# USB_to_Serial.net
KiCad netlist of a schematic drawn in EAGLE
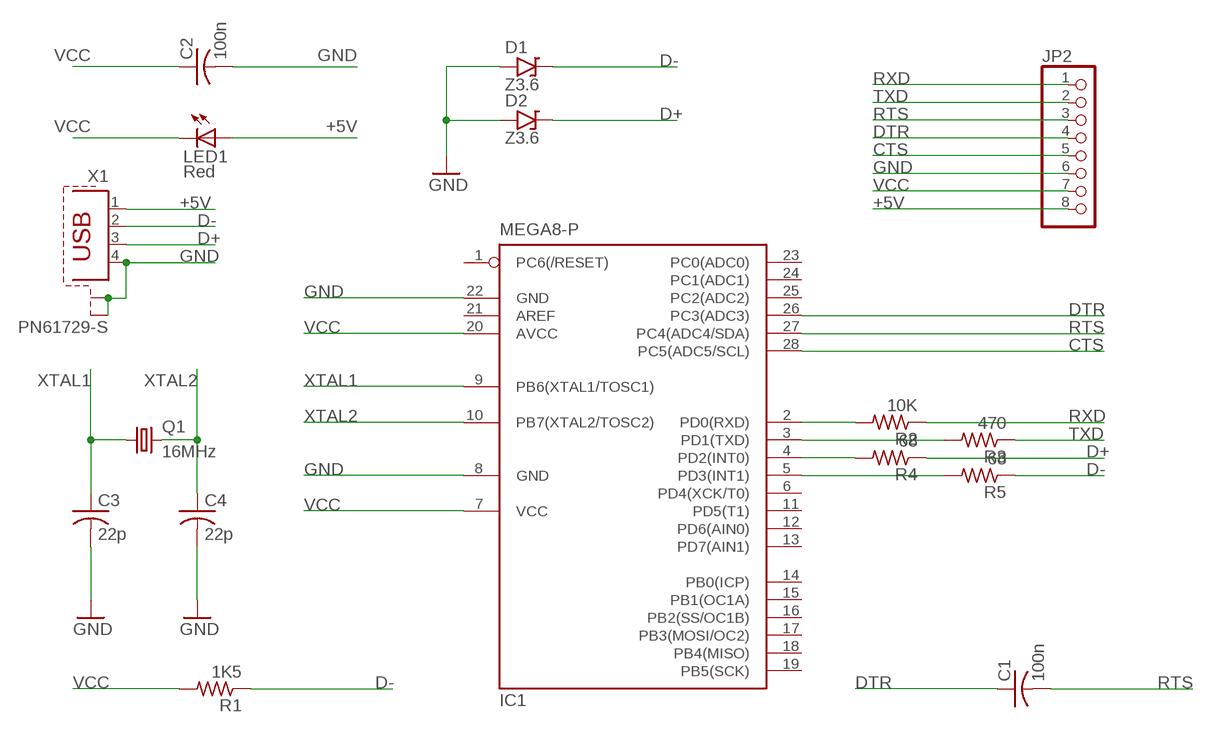
[diagram p0: schematic, sheet 1]

(export (version "E")
  (design (tool "Eeschema 10.0.6"))
  (components
    (comp (ref "C1")
      (value "100n")
      (footprint "eagle-import:C050-024X044")
      (libsource (lib "eagle-import") (part "C-US050-024X044"))
    )
    (comp (ref "C2")
      (value "100n")
      (footprint "eagle-import:C050-024X044")
      (libsource (lib "eagle-import") (part "C-US050-024X044"))
    )
    (comp (ref "C3")
      (value "22p")
      (footprint "eagle-import:C050-024X044")
      (libsource (lib "eagle-import") (part "C-US050-024X044"))
    )
    (comp (ref "C4")
      (value "22p")
      (footprint "eagle-import:C050-024X044")
      (libsource (lib "eagle-import") (part "C-US050-024X044"))
    )
    (comp (ref "D1")
      (value "Z3.6")
      (footprint "eagle-import:DO35-3")
      (libsource (lib "eagle-import") (part "1N9ZENER"))
    )
    (comp (ref "D2")
      (value "Z3.6")
      (footprint "eagle-import:DO35-3")
      (libsource (lib "eagle-import") (part "1N9ZENER"))
    )
    (comp (ref "IC1")
      (value "MEGA8-P")
      (footprint "eagle-import:DIL28-3")
      (libsource (lib "eagle-import") (part "MEGA8-P"))
    )
    (comp (ref "JP2")
      (value "PINHD-1X8/90")
      (footprint "eagle-import:1X08_90")
      (libsource (lib "eagle-import") (part "PINHD-1X8/90"))
    )
    (comp (ref "LED1")
      (value "Red")
      (footprint "eagle-import:LED3MM")
      (libsource (lib "eagle-import") (part "LED3MM"))
    )
    (comp (ref "Q1")
      (value "16MHz")
      (footprint "eagle-import:HC49_S")
      (libsource (lib "eagle-import") (part "CRYSTALHC49S"))
    )
    (comp (ref "R1")
      (value "1K5")
      (footprint "eagle-import:0207_7")
      (libsource (lib "eagle-import") (part "R-US_0207/7"))
    )
    (comp (ref "R2")
      (value "10K")
      (footprint "eagle-import:0207_7")
      (libsource (lib "eagle-import") (part "R-US_0207/7"))
    )
    (comp (ref "R3")
      (value "470")
      (footprint "eagle-import:0207_7")
      (libsource (lib "eagle-import") (part "R-US_0207/7"))
    )
    (comp (ref "R4")
      (value "68")
      (footprint "eagle-import:0207_7")
      (libsource (lib "eagle-import") (part "R-US_0207/7"))
    )
    (comp (ref "R5")
      (value "68")
      (footprint "eagle-import:0207_7")
      (libsource (lib "eagle-import") (part "R-US_0207/7"))
    )
    (comp (ref "X1")
      (value "PN61729-S")
      (footprint "eagle-import:PN61729-S")
      (libsource (lib "eagle-import") (part "PN61729-S"))
    )
  )
  (nets
    (net (code "1") (name "/+5V") (class "Default")
      (node (ref "JP2") (pin "8") (pinfunction "8_8") (pintype "passive"))
      (node (ref "LED1") (pin "A") (pinfunction "A_A") (pintype "passive"))
      (node (ref "X1") (pin "1") (pinfunction "1_1") (pintype "passive"))
    )
    (net (code "2") (name "/CTS") (class "Default")
      (node (ref "IC1") (pin "28") (pinfunction "PC5(ADC5/SCL)_28") (pintype "bidirectional"))
      (node (ref "JP2") (pin "5") (pinfunction "5_5") (pintype "passive"))
    )
    (net (code "3") (name "/D+") (class "Default")
      (node (ref "D2") (pin "C") (pinfunction "C_C") (pintype "passive"))
      (node (ref "R4") (pin "1") (pinfunction "1_1") (pintype "passive"))
      (node (ref "X1") (pin "3") (pinfunction "3_3") (pintype "passive"))
    )
    (net (code "4") (name "/D-") (class "Default")
      (node (ref "D1") (pin "C") (pinfunction "C_C") (pintype "passive"))
      (node (ref "R1") (pin "1") (pinfunction "1_1") (pintype "passive"))
      (node (ref "R5") (pin "1") (pinfunction "1_1") (pintype "passive"))
      (node (ref "X1") (pin "2") (pinfunction "2_2") (pintype "passive"))
    )
    (net (code "5") (name "/DTR") (class "Default")
      (node (ref "C1") (pin "1") (pinfunction "1_1") (pintype "passive"))
      (node (ref "IC1") (pin "26") (pinfunction "PC3(ADC3)_26") (pintype "bidirectional"))
      (node (ref "JP2") (pin "4") (pinfunction "4_4") (pintype "passive"))
    )
    (net (code "6") (name "/RTS") (class "Default")
      (node (ref "C1") (pin "2") (pinfunction "2_2") (pintype "passive"))
      (node (ref "IC1") (pin "27") (pinfunction "PC4(ADC4/SDA)_27") (pintype "bidirectional"))
      (node (ref "JP2") (pin "3") (pinfunction "3_3") (pintype "passive"))
    )
    (net (code "7") (name "/RXD") (class "Default")
      (node (ref "JP2") (pin "1") (pinfunction "1_1") (pintype "passive"))
      (node (ref "R2") (pin "1") (pinfunction "1_1") (pintype "passive"))
    )
    (net (code "8") (name "/TXD") (class "Default")
      (node (ref "JP2") (pin "2") (pinfunction "2_2") (pintype "passive"))
      (node (ref "R3") (pin "1") (pinfunction "1_1") (pintype "passive"))
    )
    (net (code "9") (name "/VCC") (class "Default")
      (node (ref "C2") (pin "1") (pinfunction "1_1") (pintype "passive"))
      (node (ref "IC1") (pin "20") (pinfunction "AVCC_20") (pintype "power_in"))
      (node (ref "IC1") (pin "7") (pinfunction "VCC_7") (pintype "power_in"))
      (node (ref "JP2") (pin "7") (pinfunction "7_7") (pintype "passive"))
      (node (ref "LED1") (pin "K") (pinfunction "C_K") (pintype "passive"))
      (node (ref "R1") (pin "2") (pinfunction "2_2") (pintype "passive"))
    )
    (net (code "10") (name "/XTAL1") (class "Default")
      (node (ref "C3") (pin "1") (pinfunction "1_1") (pintype "passive"))
      (node (ref "IC1") (pin "9") (pinfunction "PB6(XTAL1/TOSC1)_9") (pintype "bidirectional"))
      (node (ref "Q1") (pin "1") (pinfunction "1_1") (pintype "passive"))
    )
    (net (code "11") (name "/XTAL2") (class "Default")
      (node (ref "C4") (pin "1") (pinfunction "1_1") (pintype "passive"))
      (node (ref "IC1") (pin "10") (pinfunction "PB7(XTAL2/TOSC2)_10") (pintype "bidirectional"))
      (node (ref "Q1") (pin "2") (pinfunction "2_2") (pintype "passive"))
    )
    (net (code "12") (name "GND") (class "Default")
      (node (ref "C2") (pin "2") (pinfunction "2_2") (pintype "passive"))
      (node (ref "C3") (pin "2") (pinfunction "2_2") (pintype "passive"))
      (node (ref "C4") (pin "2") (pinfunction "2_2") (pintype "passive"))
      (node (ref "D1") (pin "A") (pinfunction "A_A") (pintype "passive"))
      (node (ref "D2") (pin "A") (pinfunction "A_A") (pintype "passive"))
      (node (ref "IC1") (pin "22") (pinfunction "GND_22") (pintype "power_in"))
      (node (ref "IC1") (pin "8") (pinfunction "GND_8") (pintype "power_in"))
      (node (ref "JP2") (pin "6") (pinfunction "6_6") (pintype "passive"))
      (node (ref "X1") (pin "4") (pinfunction "4_4") (pintype "passive"))
      (node (ref "X1") (pin "S1") (pinfunction "S1_S1") (pintype "passive"))
      (node (ref "X1") (pin "S2") (pinfunction "S2_S2") (pintype "passive"))
    )
    (net (code "13") (name "Net-(IC1-PD0(RXD))") (class "Default")
      (node (ref "IC1") (pin "2") (pinfunction "PD0(RXD)_2") (pintype "bidirectional"))
      (node (ref "R2") (pin "2") (pinfunction "2_2") (pintype "passive"))
    )
    (net (code "14") (name "Net-(IC1-PD1(TXD))") (class "Default")
      (node (ref "IC1") (pin "3") (pinfunction "PD1(TXD)_3") (pintype "bidirectional"))
      (node (ref "R3") (pin "2") (pinfunction "2_2") (pintype "passive"))
    )
    (net (code "15") (name "Net-(IC1-PD2(INT0))") (class "Default")
      (node (ref "IC1") (pin "4") (pinfunction "PD2(INT0)_4") (pintype "bidirectional"))
      (node (ref "R4") (pin "2") (pinfunction "2_2") (pintype "passive"))
    )
    (net (code "16") (name "Net-(IC1-PD3(INT1))") (class "Default")
      (node (ref "IC1") (pin "5") (pinfunction "PD3(INT1)_5") (pintype "bidirectional"))
      (node (ref "R5") (pin "2") (pinfunction "2_2") (pintype "passive"))
    )
    (net (code "17") (name "unconnected-(IC1-AREF-Pad21)") (class "Default")
      (node (ref "IC1") (pin "21") (pinfunction "AREF_21") (pintype "passive"))
    )
    (net (code "18") (name "unconnected-(IC1-PB0(ICP)-Pad14)") (class "Default")
      (node (ref "IC1") (pin "14") (pinfunction "PB0(ICP)_14") (pintype "bidirectional"))
    )
    (net (code "19") (name "unconnected-(IC1-PB1(OC1A)-Pad15)") (class "Default")
      (node (ref "IC1") (pin "15") (pinfunction "PB1(OC1A)_15") (pintype "bidirectional"))
    )
    (net (code "20") (name "unconnected-(IC1-PB2(SS{slash}OC1B)-Pad16)") (class "Default")
      (node (ref "IC1") (pin "16") (pinfunction "PB2(SS/OC1B)_16") (pintype "bidirectional"))
    )
    (net (code "21") (name "unconnected-(IC1-PB3(MOSI{slash}OC2)-Pad17)") (class "Default")
      (node (ref "IC1") (pin "17") (pinfunction "PB3(MOSI/OC2)_17") (pintype "bidirectional"))
    )
    (net (code "22") (name "unconnected-(IC1-PB4(MISO)-Pad18)") (class "Default")
      (node (ref "IC1") (pin "18") (pinfunction "PB4(MISO)_18") (pintype "bidirectional"))
    )
    (net (code "23") (name "unconnected-(IC1-PB5(SCK)-Pad19)") (class "Default")
      (node (ref "IC1") (pin "19") (pinfunction "PB5(SCK)_19") (pintype "bidirectional"))
    )
    (net (code "24") (name "unconnected-(IC1-PC0(ADC0)-Pad23)") (class "Default")
      (node (ref "IC1") (pin "23") (pinfunction "PC0(ADC0)_23") (pintype "bidirectional"))
    )
    (net (code "25") (name "unconnected-(IC1-PC1(ADC1)-Pad24)") (class "Default")
      (node (ref "IC1") (pin "24") (pinfunction "PC1(ADC1)_24") (pintype "bidirectional"))
    )
    (net (code "26") (name "unconnected-(IC1-PC2(ADC2)-Pad25)") (class "Default")
      (node (ref "IC1") (pin "25") (pinfunction "PC2(ADC2)_25") (pintype "bidirectional"))
    )
    (net (code "27") (name "unconnected-(IC1-PC6({slash}RESET)-Pad1)") (class "Default")
      (node (ref "IC1") (pin "1") (pinfunction "PC6(/RESET)_1") (pintype "bidirectional"))
    )
    (net (code "28") (name "unconnected-(IC1-PD4(XCK{slash}T0)-Pad6)") (class "Default")
      (node (ref "IC1") (pin "6") (pinfunction "PD4(XCK/T0)_6") (pintype "bidirectional"))
    )
    (net (code "29") (name "unconnected-(IC1-PD5(T1)-Pad11)") (class "Default")
      (node (ref "IC1") (pin "11") (pinfunction "PD5(T1)_11") (pintype "bidirectional"))
    )
    (net (code "30") (name "unconnected-(IC1-PD6(AIN0)-Pad12)") (class "Default")
      (node (ref "IC1") (pin "12") (pinfunction "PD6(AIN0)_12") (pintype "bidirectional"))
    )
    (net (code "31") (name "unconnected-(IC1-PD7(AIN1)-Pad13)") (class "Default")
      (node (ref "IC1") (pin "13") (pinfunction "PD7(AIN1)_13") (pintype "bidirectional"))
    )
  )
)
